# Top_pHAT.net
KiCad netlist of a schematic drawn in EAGLE
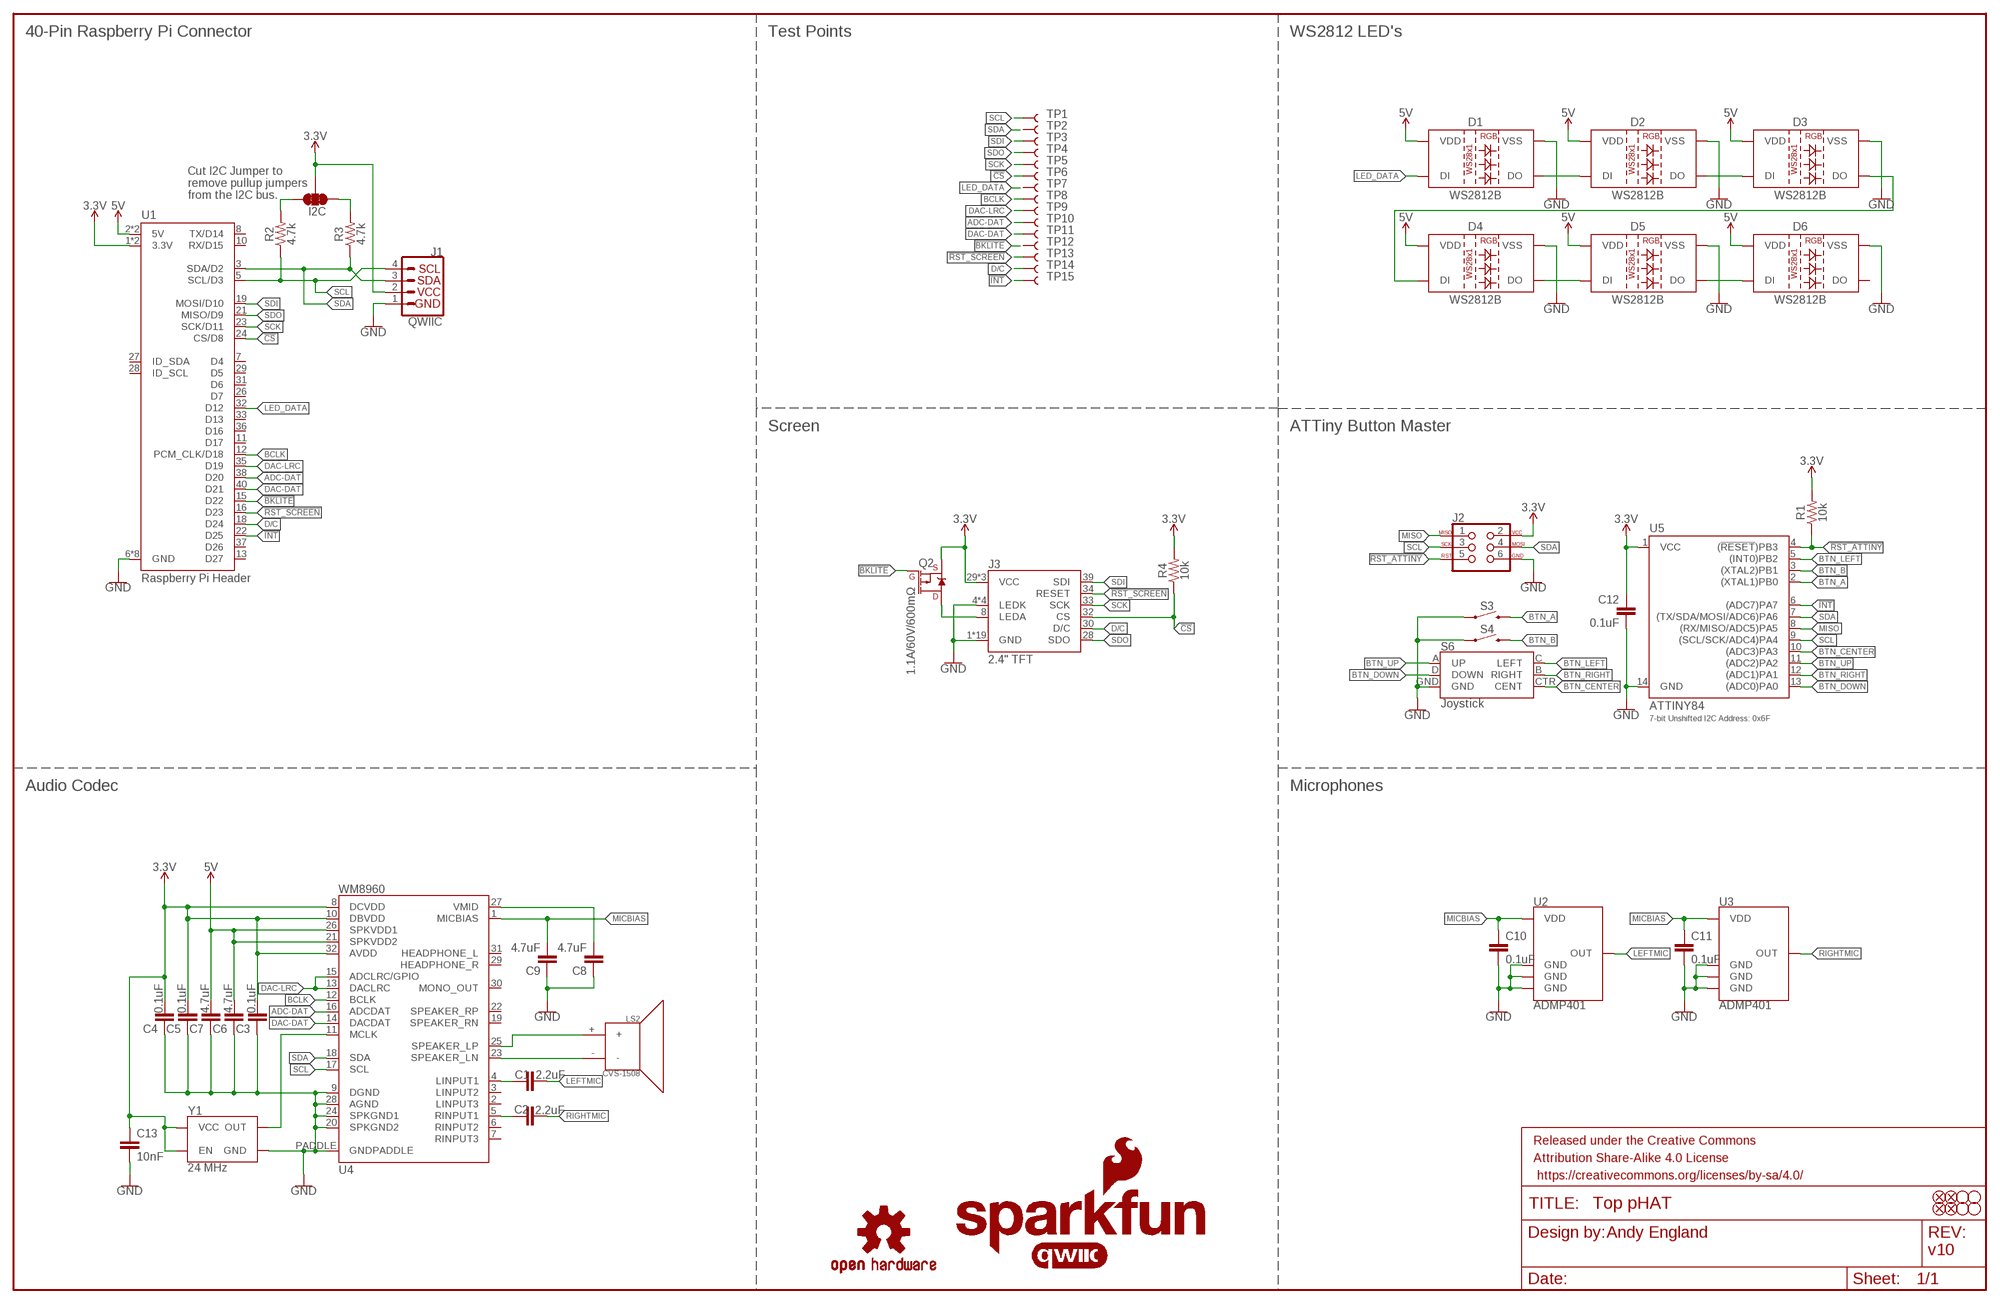
[diagram p0: schematic, sheet 1]

(export (version "E")
  (design (tool "Eeschema 10.0.6"))
  (components
    (comp (ref "C1")
      (value "2.2uF")
      (footprint "eagle-import:0603")
      (libsource (lib "eagle-import") (part "2.2UF-0603-10V-20%"))
    )
    (comp (ref "C2")
      (value "2.2uF")
      (footprint "eagle-import:0603")
      (libsource (lib "eagle-import") (part "2.2UF-0603-10V-20%"))
    )
    (comp (ref "C3")
      (value "0.1uF")
      (footprint "eagle-import:0603")
      (libsource (lib "eagle-import") (part "0.1UF-0603-25V-(+80/-20%)"))
    )
    (comp (ref "C4")
      (value "0.1uF")
      (footprint "eagle-import:0603")
      (libsource (lib "eagle-import") (part "0.1UF-0603-25V-(+80/-20%)"))
    )
    (comp (ref "C5")
      (value "0.1uF")
      (footprint "eagle-import:0603")
      (libsource (lib "eagle-import") (part "0.1UF-0603-25V-(+80/-20%)"))
    )
    (comp (ref "C6")
      (value "4.7uF")
      (footprint "eagle-import:0603")
      (libsource (lib "eagle-import") (part "4.7UF-0603-6.3V-(10%)"))
    )
    (comp (ref "C7")
      (value "4.7uF")
      (footprint "eagle-import:0603")
      (libsource (lib "eagle-import") (part "4.7UF-0603-6.3V-(10%)"))
    )
    (comp (ref "C8")
      (value "4.7uF")
      (footprint "eagle-import:0603")
      (libsource (lib "eagle-import") (part "4.7UF-0603-6.3V-(10%)"))
    )
    (comp (ref "C9")
      (value "4.7uF")
      (footprint "eagle-import:0603")
      (libsource (lib "eagle-import") (part "4.7UF-0603-6.3V-(10%)"))
    )
    (comp (ref "C10")
      (value "0.1uF")
      (footprint "eagle-import:0603")
      (libsource (lib "eagle-import") (part "0.1UF-0603-25V-(+80/-20%)"))
    )
    (comp (ref "C11")
      (value "0.1uF")
      (footprint "eagle-import:0603")
      (libsource (lib "eagle-import") (part "0.1UF-0603-25V-(+80/-20%)"))
    )
    (comp (ref "C12")
      (value "0.1uF")
      (footprint "eagle-import:0603")
      (libsource (lib "eagle-import") (part "0.1UF-0603-25V-(+80/-20%)"))
    )
    (comp (ref "C13")
      (value "10nF")
      (footprint "eagle-import:0603")
      (libsource (lib "eagle-import") (part "10NF-0603-50V-10%"))
    )
    (comp (ref "D1")
      (value "WS2812B")
      (footprint "eagle-import:WS2812B")
      (libsource (lib "eagle-import") (part "WS2812B"))
    )
    (comp (ref "D2")
      (value "WS2812B")
      (footprint "eagle-import:WS2812B")
      (libsource (lib "eagle-import") (part "WS2812B"))
    )
    (comp (ref "D3")
      (value "WS2812B")
      (footprint "eagle-import:WS2812B")
      (libsource (lib "eagle-import") (part "WS2812B"))
    )
    (comp (ref "D4")
      (value "WS2812B")
      (footprint "eagle-import:WS2812B")
      (libsource (lib "eagle-import") (part "WS2812B"))
    )
    (comp (ref "D5")
      (value "WS2812B")
      (footprint "eagle-import:WS2812B")
      (libsource (lib "eagle-import") (part "WS2812B"))
    )
    (comp (ref "D6")
      (value "WS2812B")
      (footprint "eagle-import:WS2812B")
      (libsource (lib "eagle-import") (part "WS2812B"))
    )
    (comp (ref "FD1")
      (value "FIDUCIAL1X2")
      (footprint "eagle-import:FIDUCIAL-1X2")
      (libsource (lib "eagle-import") (part "FIDUCIAL1X2"))
    )
    (comp (ref "FD2")
      (value "FIDUCIAL1X2")
      (footprint "eagle-import:FIDUCIAL-1X2")
      (libsource (lib "eagle-import") (part "FIDUCIAL1X2"))
    )
    (comp (ref "FD3")
      (value "FIDUCIAL1X2")
      (footprint "eagle-import:FIDUCIAL-1X2")
      (libsource (lib "eagle-import") (part "FIDUCIAL1X2"))
    )
    (comp (ref "FD4")
      (value "FIDUCIAL1X2")
      (footprint "eagle-import:FIDUCIAL-1X2")
      (libsource (lib "eagle-import") (part "FIDUCIAL1X2"))
    )
    (comp (ref "FRAME1")
      (value "FRAME-LEDGER")
      (footprint "eagle-import:CREATIVE_COMMONS")
      (libsource (lib "eagle-import") (part "FRAME-LEDGER"))
    )
    (comp (ref "H1")
      (value "STAND-OFFTIGHT")
      (footprint "eagle-import:STAND-OFF-TIGHT")
      (libsource (lib "eagle-import") (part "STAND-OFFTIGHT"))
    )
    (comp (ref "H2")
      (value "STAND-OFFTIGHT")
      (footprint "eagle-import:STAND-OFF-TIGHT")
      (libsource (lib "eagle-import") (part "STAND-OFFTIGHT"))
    )
    (comp (ref "H3")
      (value "STAND-OFFTIGHT")
      (footprint "eagle-import:STAND-OFF-TIGHT")
      (libsource (lib "eagle-import") (part "STAND-OFFTIGHT"))
    )
    (comp (ref "H4")
      (value "STAND-OFFTIGHT")
      (footprint "eagle-import:STAND-OFF-TIGHT")
      (libsource (lib "eagle-import") (part "STAND-OFFTIGHT"))
    )
    (comp (ref "I2C")
      (value "JUMPER-SMT_3_2-NC_TRACE_NO-SILK")
      (footprint "eagle-import:SMT-JUMPER_3_2-NC_TRACE_NO-SILK")
      (libsource (lib "eagle-import") (part "JUMPER-SMT_3_2-NC_TRACE_NO-SILK"))
    )
    (comp (ref "J1")
      (value "QWIIC")
      (footprint "eagle-import:JST04_1MM_RA")
      (libsource (lib "eagle-import") (part "QWIIC_CONNECTORJS-1MM"))
    )
    (comp (ref "J2")
      (value "AVR_SPI_PROG_3X2TESTPOINTS")
      (footprint "eagle-import:2X3_TEST_POINTS")
      (libsource (lib "eagle-import") (part "AVR_SPI_PROG_3X2TESTPOINTS"))
    )
    (comp (ref "J3")
      (value "2.4\" TFT")
      (footprint "eagle-import:FPC05040-17204")
      (libsource (lib "eagle-import") (part "4DLCD-24-320X240"))
    )
    (comp (ref "LOGO2")
      (value "SFE_LOGO_NAME_FLAME.4_INCH")
      (footprint "eagle-import:SFE_LOGO_NAME_FLAME_.4")
      (libsource (lib "eagle-import") (part "SFE_LOGO_NAME_FLAME.4_INCH"))
    )
    (comp (ref "LOGO3")
      (value "QWIIC_LOGO_4MM")
      (footprint "eagle-import:QWIIC_4MM")
      (libsource (lib "eagle-import") (part "QWIIC_LOGO_4MM"))
    )
    (comp (ref "LOGO4")
      (value "OSHW-LOGOS")
      (footprint "eagle-import:OSHW-LOGO-S")
      (libsource (lib "eagle-import") (part "OSHW-LOGOS"))
    )
    (comp (ref "LS2")
      (value "CVS-1508")
      (footprint "eagle-import:CVS-1508_PCBSPKR")
      (libsource (lib "eagle-import") (part "SPEAKERCVS-1508"))
    )
    (comp (ref "Q2")
      (value "1.1A/60V/600mΩ")
      (footprint "eagle-import:SOT23-3")
      (libsource (lib "eagle-import") (part "MOSFET_PCH-SI2309DS"))
    )
    (comp (ref "R1")
      (value "10k")
      (footprint "eagle-import:0603")
      (libsource (lib "eagle-import") (part "10KOHM-0603-1/10W-1%"))
    )
    (comp (ref "R2")
      (value "4.7k")
      (footprint "eagle-import:0603")
      (libsource (lib "eagle-import") (part "4.7KOHM-0603-1/10W-1%"))
    )
    (comp (ref "R3")
      (value "4.7k")
      (footprint "eagle-import:0603")
      (libsource (lib "eagle-import") (part "4.7KOHM-0603-1/10W-1%"))
    )
    (comp (ref "R4")
      (value "10k")
      (footprint "eagle-import:0603")
      (libsource (lib "eagle-import") (part "10KOHM-0603-1/10W-1%"))
    )
    (comp (ref "S3")
      (value "MOMENTARY-SWITCH-SPST-SMD-5.2MM-TALL")
      (footprint "eagle-import:TACTILE_SWITCH_SMD_5.2MM")
      (libsource (lib "eagle-import") (part "MOMENTARY-SWITCH-SPST-SMD-5.2MM-TALL"))
    )
    (comp (ref "S4")
      (value "MOMENTARY-SWITCH-SPST-SMD-5.2MM-TALL")
      (footprint "eagle-import:TACTILE_SWITCH_SMD_5.2MM")
      (libsource (lib "eagle-import") (part "MOMENTARY-SWITCH-SPST-SMD-5.2MM-TALL"))
    )
    (comp (ref "S6")
      (value "Joystick")
      (footprint "eagle-import:JOYSTICK_MINI")
      (libsource (lib "eagle-import") (part "JOYSTICK_MINI"))
    )
    (comp (ref "TP1")
      (value "TEST-POINT3X5")
      (footprint "eagle-import:PAD.03X.05")
      (libsource (lib "eagle-import") (part "TEST-POINT3X5"))
    )
    (comp (ref "TP2")
      (value "TEST-POINT3X5")
      (footprint "eagle-import:PAD.03X.05")
      (libsource (lib "eagle-import") (part "TEST-POINT3X5"))
    )
    (comp (ref "TP3")
      (value "TEST-POINT3X5")
      (footprint "eagle-import:PAD.03X.05")
      (libsource (lib "eagle-import") (part "TEST-POINT3X5"))
    )
    (comp (ref "TP4")
      (value "TEST-POINT3X5")
      (footprint "eagle-import:PAD.03X.05")
      (libsource (lib "eagle-import") (part "TEST-POINT3X5"))
    )
    (comp (ref "TP5")
      (value "TEST-POINT3X5")
      (footprint "eagle-import:PAD.03X.05")
      (libsource (lib "eagle-import") (part "TEST-POINT3X5"))
    )
    (comp (ref "TP6")
      (value "TEST-POINT3X5")
      (footprint "eagle-import:PAD.03X.05")
      (libsource (lib "eagle-import") (part "TEST-POINT3X5"))
    )
    (comp (ref "TP7")
      (value "TEST-POINT3X5")
      (footprint "eagle-import:PAD.03X.05")
      (libsource (lib "eagle-import") (part "TEST-POINT3X5"))
    )
    (comp (ref "TP8")
      (value "TEST-POINT3X5")
      (footprint "eagle-import:PAD.03X.05")
      (libsource (lib "eagle-import") (part "TEST-POINT3X5"))
    )
    (comp (ref "TP9")
      (value "TEST-POINT3X5")
      (footprint "eagle-import:PAD.03X.05")
      (libsource (lib "eagle-import") (part "TEST-POINT3X5"))
    )
    (comp (ref "TP10")
      (value "TEST-POINT3X5")
      (footprint "eagle-import:PAD.03X.05")
      (libsource (lib "eagle-import") (part "TEST-POINT3X5"))
    )
    (comp (ref "TP11")
      (value "TEST-POINT3X5")
      (footprint "eagle-import:PAD.03X.05")
      (libsource (lib "eagle-import") (part "TEST-POINT3X5"))
    )
    (comp (ref "TP12")
      (value "TEST-POINT3X5")
      (footprint "eagle-import:PAD.03X.05")
      (libsource (lib "eagle-import") (part "TEST-POINT3X5"))
    )
    (comp (ref "TP13")
      (value "TEST-POINT3X5")
      (footprint "eagle-import:PAD.03X.05")
      (libsource (lib "eagle-import") (part "TEST-POINT3X5"))
    )
    (comp (ref "TP14")
      (value "TEST-POINT3X5")
      (footprint "eagle-import:PAD.03X.05")
      (libsource (lib "eagle-import") (part "TEST-POINT3X5"))
    )
    (comp (ref "TP15")
      (value "TEST-POINT3X5")
      (footprint "eagle-import:PAD.03X.05")
      (libsource (lib "eagle-import") (part "TEST-POINT3X5"))
    )
    (comp (ref "U1")
      (value "Raspberry Pi Header")
      (footprint "eagle-import:RASPBERRY_PI_SHIELD_BOTTOM_ENTRY_NOHOLES")
      (libsource (lib "eagle-import") (part "RASPBERRY_PI_40BTM-NOHOLES"))
    )
    (comp (ref "U2")
      (value "ADMP401")
      (footprint "eagle-import:ADMP401")
      (libsource (lib "eagle-import") (part "ADMP401"))
    )
    (comp (ref "U3")
      (value "ADMP401")
      (footprint "eagle-import:ADMP401")
      (libsource (lib "eagle-import") (part "ADMP401"))
    )
    (comp (ref "U4")
      (value "WM8960")
      (footprint "eagle-import:QFN-32")
      (libsource (lib "eagle-import") (part "WM8960"))
    )
    (comp (ref "U5")
      (value "ATTINY84")
      (footprint "eagle-import:SO14")
      (libsource (lib "eagle-import") (part "ATTINY84"))
    )
    (comp (ref "Y1")
      (value "24 MHz")
      (footprint "eagle-import:RESONATOR-SMD-3.2X2.5")
      (libsource (lib "eagle-import") (part "OSCILLATOR-24MHZ"))
    )
  )
  (nets
    (net (code "1") (name "/~{BKLITE}") (class "Default")
      (node (ref "Q2") (pin "1") (pinfunction "G_1") (pintype "bidirectional"))
      (node (ref "TP12") (pin "P$1") (pinfunction "1_P$1") (pintype "bidirectional"))
      (node (ref "U1") (pin "15") (pinfunction "D22_15") (pintype "bidirectional"))
    )
    (net (code "2") (name "/~{CS}") (class "Default")
      (node (ref "J3") (pin "32") (pinfunction "CS_32") (pintype "bidirectional"))
      (node (ref "R4") (pin "1") (pinfunction "1_1") (pintype "passive"))
      (node (ref "TP6") (pin "P$1") (pinfunction "1_P$1") (pintype "bidirectional"))
      (node (ref "U1") (pin "24") (pinfunction "CS/D8_24") (pintype "bidirectional"))
    )
    (net (code "3") (name "/~{INT}") (class "Default")
      (node (ref "TP15") (pin "P$1") (pinfunction "1_P$1") (pintype "bidirectional"))
      (node (ref "U1") (pin "22") (pinfunction "D25_22") (pintype "bidirectional"))
      (node (ref "U5") (pin "6") (pinfunction "(ADC7)PA7_6") (pintype "bidirectional"))
    )
    (net (code "4") (name "/~{RST_ATTINY}") (class "Default")
      (node (ref "J2") (pin "5") (pinfunction "5_5") (pintype "passive"))
      (node (ref "R1") (pin "1") (pinfunction "1_1") (pintype "passive"))
      (node (ref "U5") (pin "4") (pinfunction "(~{RESET})PB3_4") (pintype "bidirectional"))
    )
    (net (code "5") (name "/~{RST_SCREEN}") (class "Default")
      (node (ref "J3") (pin "34") (pinfunction "RESET_34") (pintype "bidirectional"))
      (node (ref "TP13") (pin "P$1") (pinfunction "1_P$1") (pintype "bidirectional"))
      (node (ref "U1") (pin "16") (pinfunction "D23_16") (pintype "bidirectional"))
    )
    (net (code "6") (name "3.3V") (class "Default")
      (node (ref "C12") (pin "1") (pinfunction "1_1") (pintype "passive"))
      (node (ref "C13") (pin "1") (pinfunction "1_1") (pintype "passive"))
      (node (ref "C3") (pin "2") (pinfunction "2_2") (pintype "passive"))
      (node (ref "C4") (pin "2") (pinfunction "2_2") (pintype "passive"))
      (node (ref "C5") (pin "2") (pinfunction "2_2") (pintype "passive"))
      (node (ref "I2C") (pin "2") (pinfunction "2_2") (pintype "passive"))
      (node (ref "J1") (pin "2") (pinfunction "2_2") (pintype "power_in"))
      (node (ref "J2") (pin "2") (pinfunction "2_2") (pintype "passive"))
      (node (ref "J3") (pin "29") (pinfunction "VCC_29") (pintype "bidirectional"))
      (node (ref "J3") (pin "31") (pinfunction "VCC_31") (pintype "bidirectional"))
      (node (ref "J3") (pin "38") (pinfunction "VCC_38") (pintype "bidirectional"))
      (node (ref "Q2") (pin "2") (pinfunction "S_2") (pintype "bidirectional"))
      (node (ref "R1") (pin "2") (pinfunction "2_2") (pintype "passive"))
      (node (ref "R4") (pin "2") (pinfunction "2_2") (pintype "passive"))
      (node (ref "U1") (pin "1") (pinfunction "3.3V_1") (pintype "bidirectional"))
      (node (ref "U1") (pin "17") (pinfunction "3.3V_17") (pintype "bidirectional"))
      (node (ref "U4") (pin "10") (pinfunction "DBVDD_10") (pintype "bidirectional"))
      (node (ref "U4") (pin "32") (pinfunction "AVDD_32") (pintype "bidirectional"))
      (node (ref "U4") (pin "8") (pinfunction "DCVDD_8") (pintype "bidirectional"))
      (node (ref "U5") (pin "1") (pinfunction "VCC_1") (pintype "bidirectional"))
      (node (ref "Y1") (pin "1") (pinfunction "EN_1") (pintype "bidirectional"))
      (node (ref "Y1") (pin "4") (pinfunction "VCC_4") (pintype "bidirectional"))
    )
    (net (code "7") (name "5V") (class "Default")
      (node (ref "C6") (pin "2") (pinfunction "2_2") (pintype "passive"))
      (node (ref "C7") (pin "2") (pinfunction "2_2") (pintype "passive"))
      (node (ref "D1") (pin "1") (pinfunction "VDD_1") (pintype "bidirectional"))
      (node (ref "D2") (pin "1") (pinfunction "VDD_1") (pintype "bidirectional"))
      (node (ref "D3") (pin "1") (pinfunction "VDD_1") (pintype "bidirectional"))
      (node (ref "D4") (pin "1") (pinfunction "VDD_1") (pintype "bidirectional"))
      (node (ref "D5") (pin "1") (pinfunction "VDD_1") (pintype "bidirectional"))
      (node (ref "D6") (pin "1") (pinfunction "VDD_1") (pintype "bidirectional"))
      (node (ref "U1") (pin "2") (pinfunction "5V_2") (pintype "bidirectional"))
      (node (ref "U1") (pin "4") (pinfunction "5V_4") (pintype "bidirectional"))
      (node (ref "U4") (pin "21") (pinfunction "SPKVDD2_21") (pintype "bidirectional"))
      (node (ref "U4") (pin "26") (pinfunction "SPKVDD1_26") (pintype "bidirectional"))
    )
    (net (code "8") (name "ADC-DAT") (class "Default")
      (node (ref "TP10") (pin "P$1") (pinfunction "1_P$1") (pintype "bidirectional"))
      (node (ref "U1") (pin "38") (pinfunction "D20_38") (pintype "bidirectional"))
      (node (ref "U4") (pin "16") (pinfunction "ADCDAT_16") (pintype "bidirectional"))
    )
    (net (code "9") (name "BCLK") (class "Default")
      (node (ref "TP8") (pin "P$1") (pinfunction "1_P$1") (pintype "bidirectional"))
      (node (ref "U1") (pin "12") (pinfunction "PCM_CLK/D18_12") (pintype "bidirectional"))
      (node (ref "U4") (pin "12") (pinfunction "BCLK_12") (pintype "bidirectional"))
    )
    (net (code "10") (name "BTN_A") (class "Default")
      (node (ref "S3") (pin "3") (pinfunction "2_3") (pintype "passive"))
      (node (ref "U5") (pin "2") (pinfunction "(XTAL1)PB0_2") (pintype "bidirectional"))
    )
    (net (code "11") (name "BTN_B") (class "Default")
      (node (ref "S4") (pin "3") (pinfunction "2_3") (pintype "passive"))
      (node (ref "U5") (pin "3") (pinfunction "(XTAL2)PB1_3") (pintype "bidirectional"))
    )
    (net (code "12") (name "BTN_CENTER") (class "Default")
      (node (ref "S6") (pin "CTR") (pinfunction "CENT_CTR") (pintype "bidirectional"))
      (node (ref "U5") (pin "10") (pinfunction "(ADC3)PA3_10") (pintype "bidirectional"))
    )
    (net (code "13") (name "BTN_DOWN") (class "Default")
      (node (ref "S6") (pin "D") (pinfunction "DOWN_D") (pintype "bidirectional"))
      (node (ref "U5") (pin "13") (pinfunction "(ADC0)PA0_13") (pintype "bidirectional"))
    )
    (net (code "14") (name "BTN_LEFT") (class "Default")
      (node (ref "S6") (pin "C") (pinfunction "LEFT_C") (pintype "bidirectional"))
      (node (ref "U5") (pin "5") (pinfunction "(INT0)PB2_5") (pintype "bidirectional"))
    )
    (net (code "15") (name "BTN_RIGHT") (class "Default")
      (node (ref "S6") (pin "B") (pinfunction "RIGHT_B") (pintype "bidirectional"))
      (node (ref "U5") (pin "12") (pinfunction "(ADC1)PA1_12") (pintype "bidirectional"))
    )
    (net (code "16") (name "BTN_UP") (class "Default")
      (node (ref "S6") (pin "A") (pinfunction "UP_A") (pintype "bidirectional"))
      (node (ref "U5") (pin "11") (pinfunction "(ADC2)PA2_11") (pintype "bidirectional"))
    )
    (net (code "17") (name "DAC-DAT") (class "Default")
      (node (ref "TP11") (pin "P$1") (pinfunction "1_P$1") (pintype "bidirectional"))
      (node (ref "U1") (pin "40") (pinfunction "D21_40") (pintype "bidirectional"))
      (node (ref "U4") (pin "14") (pinfunction "DACDAT_14") (pintype "bidirectional"))
    )
    (net (code "18") (name "DAC-LRC") (class "Default")
      (node (ref "TP9") (pin "P$1") (pinfunction "1_P$1") (pintype "bidirectional"))
      (node (ref "U1") (pin "35") (pinfunction "D19_35") (pintype "bidirectional"))
      (node (ref "U4") (pin "13") (pinfunction "DACLRC_13") (pintype "bidirectional"))
      (node (ref "U4") (pin "15") (pinfunction "ADCLRC/GPIO_15") (pintype "bidirectional"))
    )
    (net (code "19") (name "D{slash}C") (class "Default")
      (node (ref "J3") (pin "30") (pinfunction "D/C_30") (pintype "bidirectional"))
      (node (ref "TP14") (pin "P$1") (pinfunction "1_P$1") (pintype "bidirectional"))
      (node (ref "U1") (pin "18") (pinfunction "D24_18") (pintype "bidirectional"))
    )
    (net (code "20") (name "GND") (class "Default")
      (node (ref "C10") (pin "2") (pinfunction "2_2") (pintype "passive"))
      (node (ref "C11") (pin "2") (pinfunction "2_2") (pintype "passive"))
      (node (ref "C12") (pin "2") (pinfunction "2_2") (pintype "passive"))
      (node (ref "C13") (pin "2") (pinfunction "2_2") (pintype "passive"))
      (node (ref "C3") (pin "1") (pinfunction "1_1") (pintype "passive"))
      (node (ref "C4") (pin "1") (pinfunction "1_1") (pintype "passive"))
      (node (ref "C5") (pin "1") (pinfunction "1_1") (pintype "passive"))
      (node (ref "C6") (pin "1") (pinfunction "1_1") (pintype "passive"))
      (node (ref "C7") (pin "1") (pinfunction "1_1") (pintype "passive"))
      (node (ref "C8") (pin "1") (pinfunction "1_1") (pintype "passive"))
      (node (ref "C9") (pin "1") (pinfunction "1_1") (pintype "passive"))
      (node (ref "D1") (pin "3") (pinfunction "VSS_3") (pintype "bidirectional"))
      (node (ref "D2") (pin "3") (pinfunction "VSS_3") (pintype "bidirectional"))
      (node (ref "D3") (pin "3") (pinfunction "VSS_3") (pintype "bidirectional"))
      (node (ref "D4") (pin "3") (pinfunction "VSS_3") (pintype "bidirectional"))
      (node (ref "D5") (pin "3") (pinfunction "VSS_3") (pintype "bidirectional"))
      (node (ref "D6") (pin "3") (pinfunction "VSS_3") (pintype "bidirectional"))
      (node (ref "J1") (pin "1") (pinfunction "1_1") (pintype "power_in"))
      (node (ref "J2") (pin "6") (pinfunction "6_6") (pintype "passive"))
      (node (ref "J3") (pin "1") (pinfunction "GND_1") (pintype "bidirectional"))
      (node (ref "J3") (pin "11") (pinfunction "GND_11") (pintype "bidirectional"))
      (node (ref "J3") (pin "12") (pinfunction "GND_12") (pintype "bidirectional"))
      (node (ref "J3") (pin "13") (pinfunction "GND_13") (pintype "bidirectional"))
      (node (ref "J3") (pin "14") (pinfunction "GND_14") (pintype "bidirectional"))
      (node (ref "J3") (pin "15") (pinfunction "GND_15") (pintype "bidirectional"))
      (node (ref "J3") (pin "16") (pinfunction "GND_16") (pintype "bidirectional"))
      (node (ref "J3") (pin "17") (pinfunction "GND_17") (pintype "bidirectional"))
      (node (ref "J3") (pin "18") (pinfunction "GND_18") (pintype "bidirectional"))
      (node (ref "J3") (pin "19") (pinfunction "GND_19") (pintype "bidirectional"))
      (node (ref "J3") (pin "20") (pinfunction "GND_20") (pintype "bidirectional"))
      (node (ref "J3") (pin "21") (pinfunction "GND_21") (pintype "bidirectional"))
      (node (ref "J3") (pin "22") (pinfunction "GND_22") (pintype "bidirectional"))
      (node (ref "J3") (pin "23") (pinfunction "GND_23") (pintype "bidirectional"))
      (node (ref "J3") (pin "24") (pinfunction "GND_24") (pintype "bidirectional"))
      (node (ref "J3") (pin "25") (pinfunction "GND_25") (pintype "bidirectional"))
      (node (ref "J3") (pin "26") (pinfunction "GND_26") (pintype "bidirectional"))
      (node (ref "J3") (pin "27") (pinfunction "GND_27") (pintype "bidirectional"))
      (node (ref "J3") (pin "4") (pinfunction "LEDK_4") (pintype "bidirectional"))
      (node (ref "J3") (pin "40") (pinfunction "GND_40") (pintype "bidirectional"))
      (node (ref "J3") (pin "5") (pinfunction "LEDK_5") (pintype "bidirectional"))
      (node (ref "J3") (pin "6") (pinfunction "LEDK_6") (pintype "bidirectional"))
      (node (ref "J3") (pin "7") (pinfunction "LEDK_7") (pintype "bidirectional"))
      (node (ref "S3") (pin "1") (pinfunction "1_1") (pintype "passive"))
      (node (ref "S4") (pin "1") (pinfunction "1_1") (pintype "passive"))
      (node (ref "S6") (pin "GND") (pinfunction "GND_GND") (pintype "bidirectional"))
      (node (ref "U1") (pin "14") (pinfunction "GND_14") (pintype "bidirectional"))
      (node (ref "U1") (pin "20") (pinfunction "GND_20") (pintype "bidirectional"))
      (node (ref "U1") (pin "25") (pinfunction "GND_25") (pintype "bidirectional"))
      (node (ref "U1") (pin "30") (pinfunction "GND_30") (pintype "bidirectional"))
      (node (ref "U1") (pin "34") (pinfunction "GND_34") (pintype "bidirectional"))
      (node (ref "U1") (pin "39") (pinfunction "GND_39") (pintype "bidirectional"))
      (node (ref "U1") (pin "6") (pinfunction "GND_6") (pintype "bidirectional"))
      (node (ref "U1") (pin "9") (pinfunction "GND_9") (pintype "bidirectional"))
      (node (ref "U2") (pin "2") (pinfunction "GND_2") (pintype "bidirectional"))
      (node (ref "U2") (pin "4") (pinfunction "GND_4") (pintype "bidirectional"))
      (node (ref "U2") (pin "6") (pinfunction "GND_6") (pintype "bidirectional"))
      (node (ref "U3") (pin "2") (pinfunction "GND_2") (pintype "bidirectional"))
      (node (ref "U3") (pin "4") (pinfunction "GND_4") (pintype "bidirectional"))
      (node (ref "U3") (pin "6") (pinfunction "GND_6") (pintype "bidirectional"))
      (node (ref "U4") (pin "20") (pinfunction "SPKGND2_20") (pintype "bidirectional"))
      (node (ref "U4") (pin "24") (pinfunction "SPKGND1_24") (pintype "bidirectional"))
      (node (ref "U4") (pin "28") (pinfunction "AGND_28") (pintype "bidirectional"))
      (node (ref "U4") (pin "9") (pinfunction "DGND_9") (pintype "bidirectional"))
      (node (ref "U4") (pin "PADDLE") (pinfunction "GNDPADDLE_PADDLE") (pintype "bidirectional"))
      (node (ref "U5") (pin "14") (pinfunction "GND_14") (pintype "bidirectional"))
      (node (ref "Y1") (pin "2") (pinfunction "GND_2") (pintype "bidirectional"))
    )
    (net (code "21") (name "LED_DATA") (class "Default")
      (node (ref "D1") (pin "4") (pinfunction "DI_4") (pintype "bidirectional"))
      (node (ref "TP7") (pin "P$1") (pinfunction "1_P$1") (pintype "bidirectional"))
      (node (ref "U1") (pin "32") (pinfunction "D12_32") (pintype "bidirectional"))
    )
    (net (code "22") (name "LEFTMIC") (class "Default")
      (node (ref "C1") (pin "2") (pinfunction "2_2") (pintype "passive"))
      (node (ref "U2") (pin "1") (pinfunction "OUT_1") (pintype "bidirectional"))
    )
    (net (code "23") (name "MICBIAS") (class "Default")
      (node (ref "C10") (pin "1") (pinfunction "1_1") (pintype "passive"))
      (node (ref "C11") (pin "1") (pinfunction "1_1") (pintype "passive"))
      (node (ref "C9") (pin "2") (pinfunction "2_2") (pintype "passive"))
      (node (ref "U2") (pin "5") (pinfunction "VDD_5") (pintype "bidirectional"))
      (node (ref "U3") (pin "5") (pinfunction "VDD_5") (pintype "bidirectional"))
      (node (ref "U4") (pin "1") (pinfunction "MICBIAS_1") (pintype "bidirectional"))
    )
    (net (code "24") (name "MISO") (class "Default")
      (node (ref "J2") (pin "1") (pinfunction "1_1") (pintype "passive"))
      (node (ref "U5") (pin "8") (pinfunction "(RX/MISO/ADC5)PA5_8") (pintype "bidirectional"))
    )
    (net (code "25") (name "Net-(D1-DO)") (class "Default")
      (node (ref "D1") (pin "2") (pinfunction "DO_2") (pintype "bidirectional"))
      (node (ref "D2") (pin "4") (pinfunction "DI_4") (pintype "bidirectional"))
    )
    (net (code "26") (name "Net-(D2-DO)") (class "Default")
      (node (ref "D2") (pin "2") (pinfunction "DO_2") (pintype "bidirectional"))
      (node (ref "D3") (pin "4") (pinfunction "DI_4") (pintype "bidirectional"))
    )
    (net (code "27") (name "Net-(D3-DO)") (class "Default")
      (node (ref "D3") (pin "2") (pinfunction "DO_2") (pintype "bidirectional"))
      (node (ref "D4") (pin "4") (pinfunction "DI_4") (pintype "bidirectional"))
    )
    (net (code "28") (name "Net-(D4-DO)") (class "Default")
      (node (ref "D4") (pin "2") (pinfunction "DO_2") (pintype "bidirectional"))
      (node (ref "D5") (pin "4") (pinfunction "DI_4") (pintype "bidirectional"))
    )
    (net (code "29") (name "Net-(D5-DO)") (class "Default")
      (node (ref "D5") (pin "2") (pinfunction "DO_2") (pintype "bidirectional"))
      (node (ref "D6") (pin "4") (pinfunction "DI_4") (pintype "bidirectional"))
    )
    (net (code "30") (name "Net-(I2C-Pad1)") (class "Default")
      (node (ref "I2C") (pin "1") (pinfunction "1_1") (pintype "passive"))
      (node (ref "R3") (pin "2") (pinfunction "2_2") (pintype "passive"))
    )
    (net (code "31") (name "Net-(I2C-Pad3)") (class "Default")
      (node (ref "I2C") (pin "3") (pinfunction "3_3") (pintype "passive"))
      (node (ref "R2") (pin "2") (pinfunction "2_2") (pintype "passive"))
    )
    (net (code "32") (name "Net-(J3-LEDA)") (class "Default")
      (node (ref "J3") (pin "8") (pinfunction "LEDA_8") (pintype "bidirectional"))
      (node (ref "Q2") (pin "3") (pinfunction "D_3") (pintype "bidirectional"))
    )
    (net (code "33") (name "Net-(U4-LINPUT1)") (class "Default")
      (node (ref "C1") (pin "1") (pinfunction "1_1") (pintype "passive"))
      (node (ref "U4") (pin "4") (pinfunction "LINPUT1_4") (pintype "bidirectional"))
    )
    (net (code "34") (name "Net-(U4-MCLK)") (class "Default")
      (node (ref "U4") (pin "11") (pinfunction "MCLK_11") (pintype "bidirectional"))
      (node (ref "Y1") (pin "3") (pinfunction "OUT_3") (pintype "bidirectional"))
    )
    (net (code "35") (name "Net-(U4-RINPUT1)") (class "Default")
      (node (ref "C2") (pin "1") (pinfunction "1_1") (pintype "passive"))
      (node (ref "U4") (pin "5") (pinfunction "RINPUT1_5") (pintype "bidirectional"))
    )
    (net (code "36") (name "Net-(U4-SPEAKER_LN)") (class "Default")
      (node (ref "LS2") (pin "-") (pinfunction "-_-") (pintype "bidirectional"))
      (node (ref "U4") (pin "23") (pinfunction "SPEAKER_LN_23") (pintype "bidirectional"))
    )
    (net (code "37") (name "Net-(U4-SPEAKER_LP)") (class "Default")
      (node (ref "LS2") (pin "+") (pinfunction "+_+") (pintype "bidirectional"))
      (node (ref "U4") (pin "25") (pinfunction "SPEAKER_LP_25") (pintype "bidirectional"))
    )
    (net (code "38") (name "Net-(U4-VMID)") (class "Default")
      (node (ref "C8") (pin "2") (pinfunction "2_2") (pintype "passive"))
      (node (ref "U4") (pin "27") (pinfunction "VMID_27") (pintype "bidirectional"))
    )
    (net (code "39") (name "RIGHTMIC") (class "Default")
      (node (ref "C2") (pin "2") (pinfunction "2_2") (pintype "passive"))
      (node (ref "U3") (pin "1") (pinfunction "OUT_1") (pintype "bidirectional"))
    )
    (net (code "40") (name "SCK") (class "Default")
      (node (ref "J3") (pin "33") (pinfunction "SCK_33") (pintype "bidirectional"))
      (node (ref "TP5") (pin "P$1") (pinfunction "1_P$1") (pintype "bidirectional"))
      (node (ref "U1") (pin "23") (pinfunction "SCK/D11_23") (pintype "bidirectional"))
    )
    (net (code "41") (name "SCL") (class "Default")
      (node (ref "J1") (pin "4") (pinfunction "4_4") (pintype "passive"))
      (node (ref "J2") (pin "3") (pinfunction "3_3") (pintype "passive"))
      (node (ref "R2") (pin "1") (pinfunction "1_1") (pintype "passive"))
      (node (ref "TP1") (pin "P$1") (pinfunction "1_P$1") (pintype "bidirectional"))
      (node (ref "U1") (pin "5") (pinfunction "SCL/D3_5") (pintype "bidirectional"))
      (node (ref "U4") (pin "17") (pinfunction "SCL_17") (pintype "bidirectional"))
      (node (ref "U5") (pin "9") (pinfunction "(SCL/SCK/ADC4)PA4_9") (pintype "bidirectional"))
    )
    (net (code "42") (name "SDA") (class "Default")
      (node (ref "J1") (pin "3") (pinfunction "3_3") (pintype "passive"))
      (node (ref "J2") (pin "4") (pinfunction "4_4") (pintype "passive"))
      (node (ref "R3") (pin "1") (pinfunction "1_1") (pintype "passive"))
      (node (ref "TP2") (pin "P$1") (pinfunction "1_P$1") (pintype "bidirectional"))
      (node (ref "U1") (pin "3") (pinfunction "SDA/D2_3") (pintype "bidirectional"))
      (node (ref "U4") (pin "18") (pinfunction "SDA_18") (pintype "bidirectional"))
      (node (ref "U5") (pin "7") (pinfunction "(TX/SDA/MOSI/ADC6)PA6_7") (pintype "bidirectional"))
    )
    (net (code "43") (name "SDI") (class "Default")
      (node (ref "J3") (pin "39") (pinfunction "SDI_39") (pintype "bidirectional"))
      (node (ref "TP3") (pin "P$1") (pinfunction "1_P$1") (pintype "bidirectional"))
      (node (ref "U1") (pin "19") (pinfunction "MOSI/D10_19") (pintype "bidirectional"))
    )
    (net (code "44") (name "SDO") (class "Default")
      (node (ref "J3") (pin "28") (pinfunction "SDO_28") (pintype "bidirectional"))
      (node (ref "TP4") (pin "P$1") (pinfunction "1_P$1") (pintype "bidirectional"))
      (node (ref "U1") (pin "21") (pinfunction "MISO/D9_21") (pintype "bidirectional"))
    )
    (net (code "45") (name "unconnected-(D6-DO-Pad2)") (class "Default")
      (node (ref "D6") (pin "2") (pinfunction "DO_2") (pintype "bidirectional"))
    )
    (net (code "46") (name "unconnected-(U1-D4-Pad7)") (class "Default")
      (node (ref "U1") (pin "7") (pinfunction "D4_7") (pintype "bidirectional"))
    )
    (net (code "47") (name "unconnected-(U1-D5-Pad29)") (class "Default")
      (node (ref "U1") (pin "29") (pinfunction "D5_29") (pintype "bidirectional"))
    )
    (net (code "48") (name "unconnected-(U1-D6-Pad31)") (class "Default")
      (node (ref "U1") (pin "31") (pinfunction "D6_31") (pintype "bidirectional"))
    )
    (net (code "49") (name "unconnected-(U1-D7-Pad26)") (class "Default")
      (node (ref "U1") (pin "26") (pinfunction "D7_26") (pintype "bidirectional"))
    )
    (net (code "50") (name "unconnected-(U1-D13-Pad33)") (class "Default")
      (node (ref "U1") (pin "33") (pinfunction "D13_33") (pintype "bidirectional"))
    )
    (net (code "51") (name "unconnected-(U1-D16-Pad36)") (class "Default")
      (node (ref "U1") (pin "36") (pinfunction "D16_36") (pintype "bidirectional"))
    )
    (net (code "52") (name "unconnected-(U1-D17-Pad11)") (class "Default")
      (node (ref "U1") (pin "11") (pinfunction "D17_11") (pintype "bidirectional"))
    )
    (net (code "53") (name "unconnected-(U1-D26-Pad37)") (class "Default")
      (node (ref "U1") (pin "37") (pinfunction "D26_37") (pintype "bidirectional"))
    )
    (net (code "54") (name "unconnected-(U1-D27-Pad13)") (class "Default")
      (node (ref "U1") (pin "13") (pinfunction "D27_13") (pintype "bidirectional"))
    )
    (net (code "55") (name "unconnected-(U1-ID_SCL-Pad28)") (class "Default")
      (node (ref "U1") (pin "28") (pinfunction "ID_SCL_28") (pintype "bidirectional"))
    )
    (net (code "56") (name "unconnected-(U1-ID_SDA-Pad27)") (class "Default")
      (node (ref "U1") (pin "27") (pinfunction "ID_SDA_27") (pintype "bidirectional"))
    )
    (net (code "57") (name "unconnected-(U1-RX{slash}D15-Pad10)") (class "Default")
      (node (ref "U1") (pin "10") (pinfunction "RX/D15_10") (pintype "bidirectional"))
    )
    (net (code "58") (name "unconnected-(U1-TX{slash}D14-Pad8)") (class "Default")
      (node (ref "U1") (pin "8") (pinfunction "TX/D14_8") (pintype "bidirectional"))
    )
    (net (code "59") (name "unconnected-(U4-HEADPHONE_L-Pad31)") (class "Default")
      (node (ref "U4") (pin "31") (pinfunction "HEADPHONE_L_31") (pintype "bidirectional"))
    )
    (net (code "60") (name "unconnected-(U4-HEADPHONE_R-Pad29)") (class "Default")
      (node (ref "U4") (pin "29") (pinfunction "HEADPHONE_R_29") (pintype "bidirectional"))
    )
    (net (code "61") (name "unconnected-(U4-LINPUT2-Pad3)") (class "Default")
      (node (ref "U4") (pin "3") (pinfunction "LINPUT2_3") (pintype "bidirectional"))
    )
    (net (code "62") (name "unconnected-(U4-LINPUT3-Pad2)") (class "Default")
      (node (ref "U4") (pin "2") (pinfunction "LINPUT3_2") (pintype "bidirectional"))
    )
    (net (code "63") (name "unconnected-(U4-MONO_OUT-Pad30)") (class "Default")
      (node (ref "U4") (pin "30") (pinfunction "MONO_OUT_30") (pintype "bidirectional"))
    )
    (net (code "64") (name "unconnected-(U4-RINPUT2-Pad6)") (class "Default")
      (node (ref "U4") (pin "6") (pinfunction "RINPUT2_6") (pintype "bidirectional"))
    )
    (net (code "65") (name "unconnected-(U4-RINPUT3-Pad7)") (class "Default")
      (node (ref "U4") (pin "7") (pinfunction "RINPUT3_7") (pintype "bidirectional"))
    )
    (net (code "66") (name "unconnected-(U4-SPEAKER_RN-Pad19)") (class "Default")
      (node (ref "U4") (pin "19") (pinfunction "SPEAKER_RN_19") (pintype "bidirectional"))
    )
    (net (code "67") (name "unconnected-(U4-SPEAKER_RP-Pad22)") (class "Default")
      (node (ref "U4") (pin "22") (pinfunction "SPEAKER_RP_22") (pintype "bidirectional"))
    )
  )
)
